# HMC5883_module.net
KiCad netlist of a schematic drawn in Altium Designer
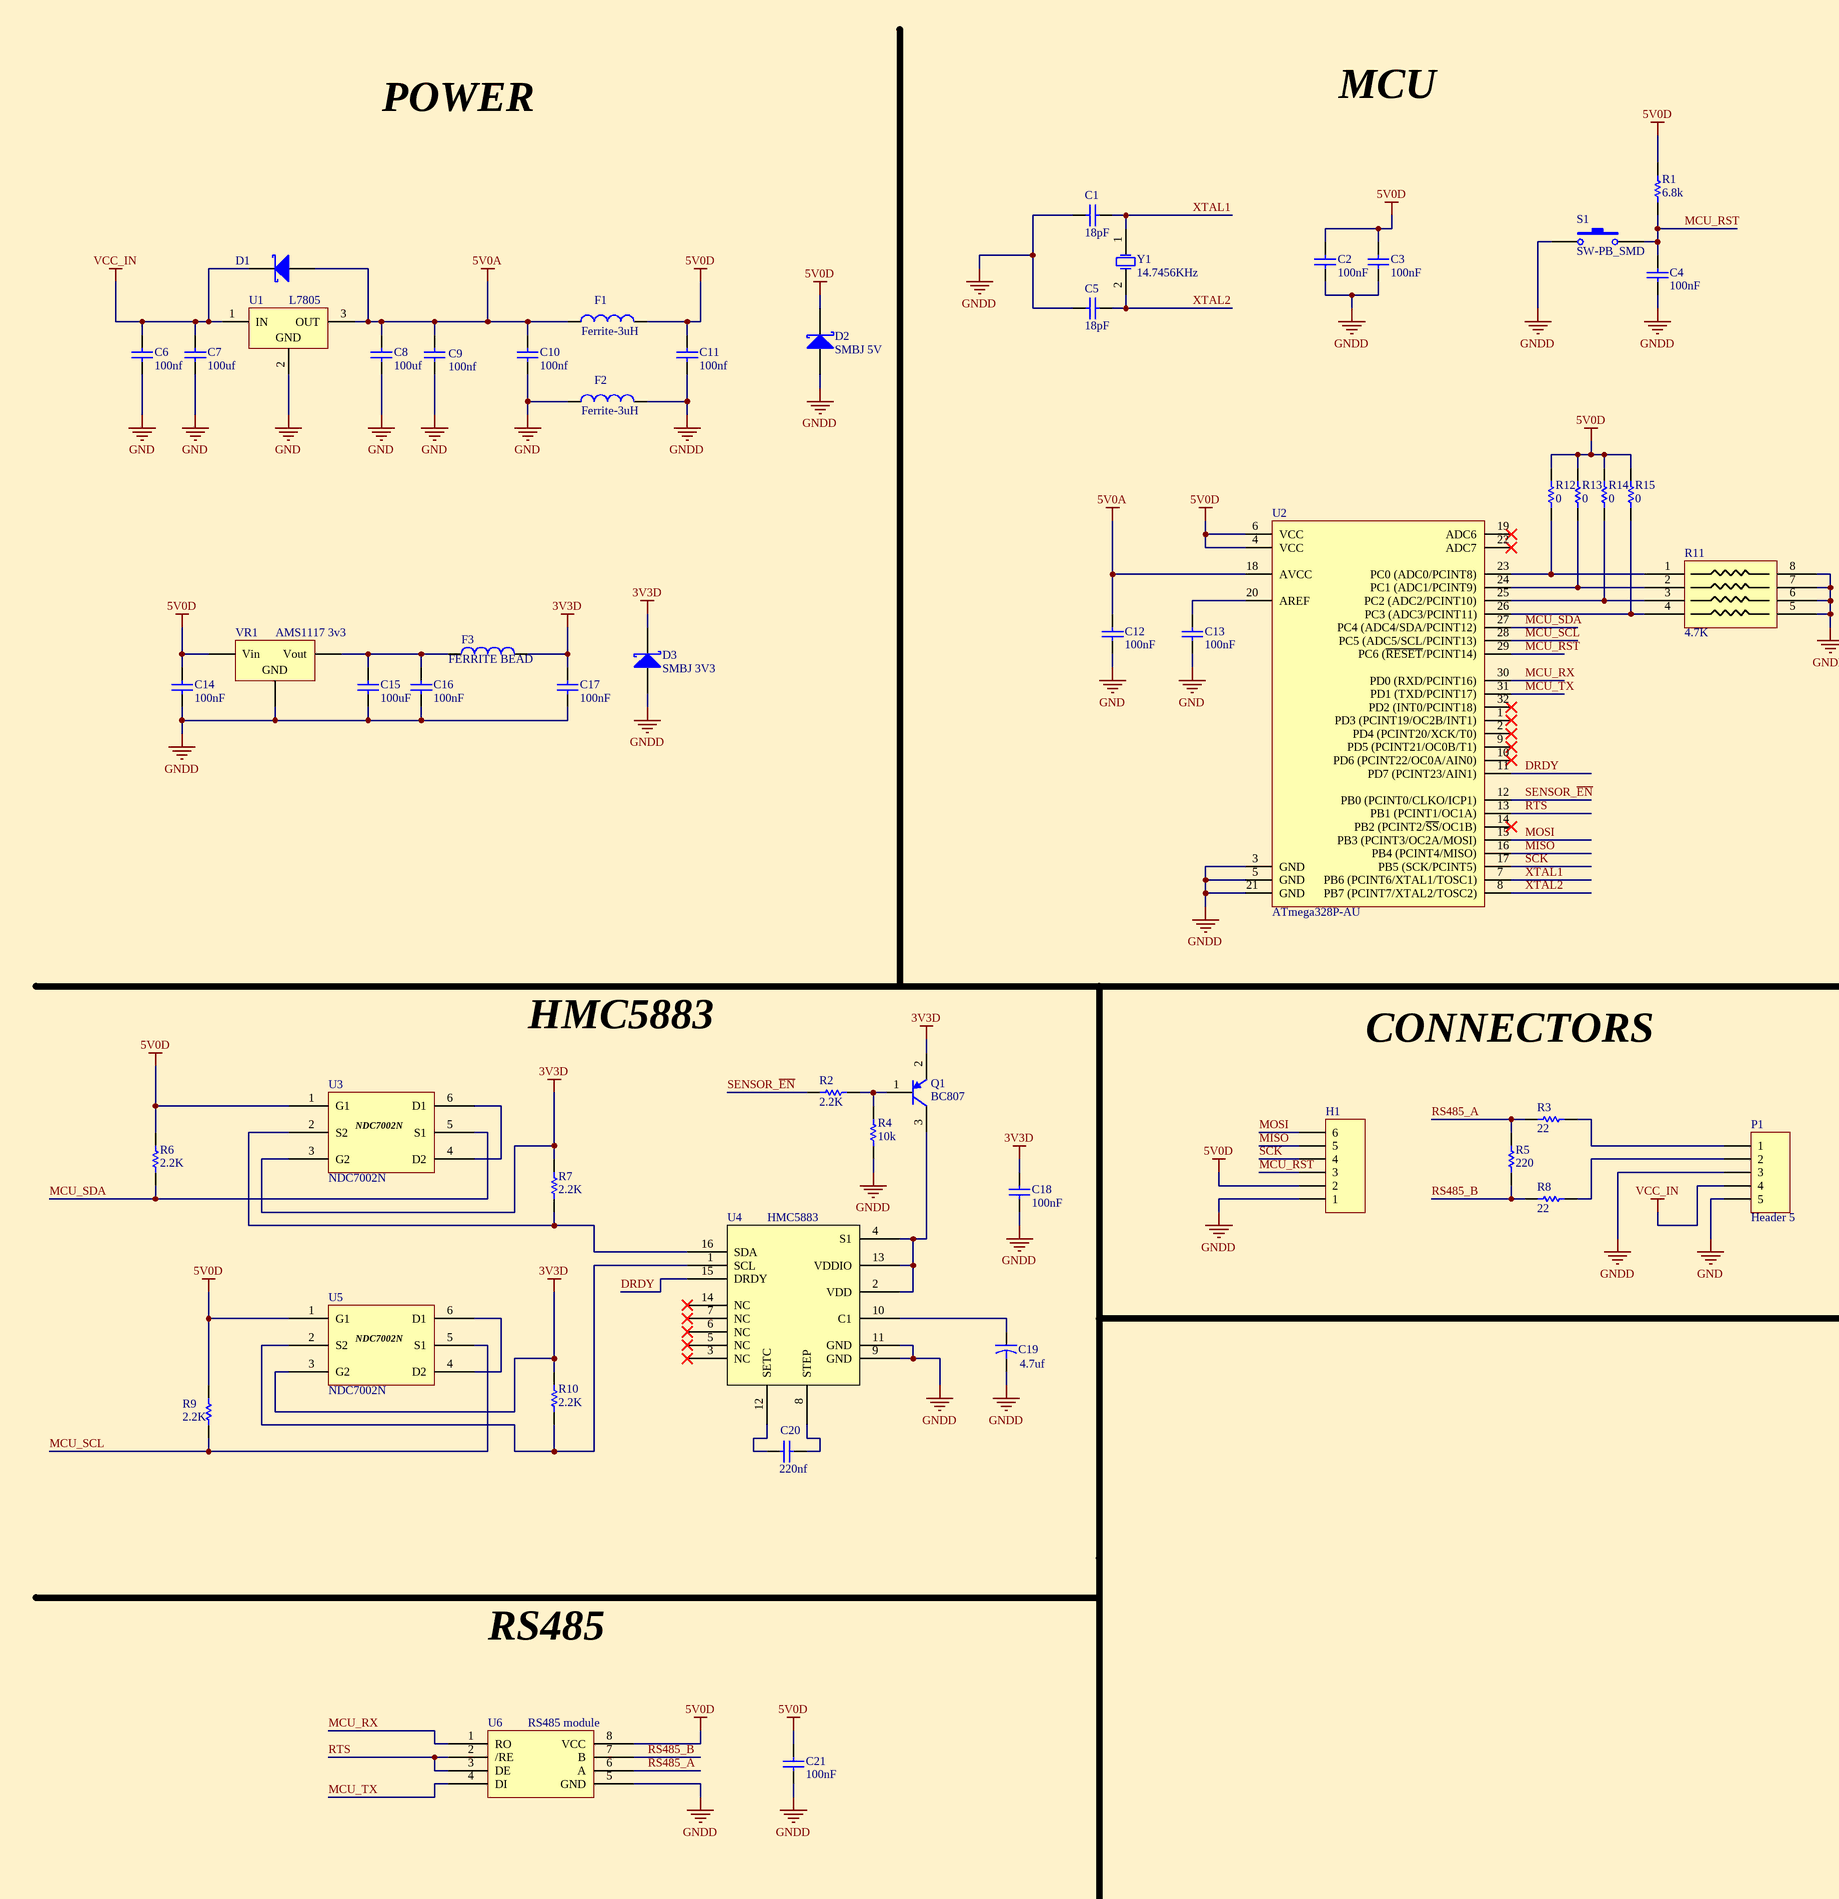
[diagram p0: HMC5883_module.SchDoc, left]
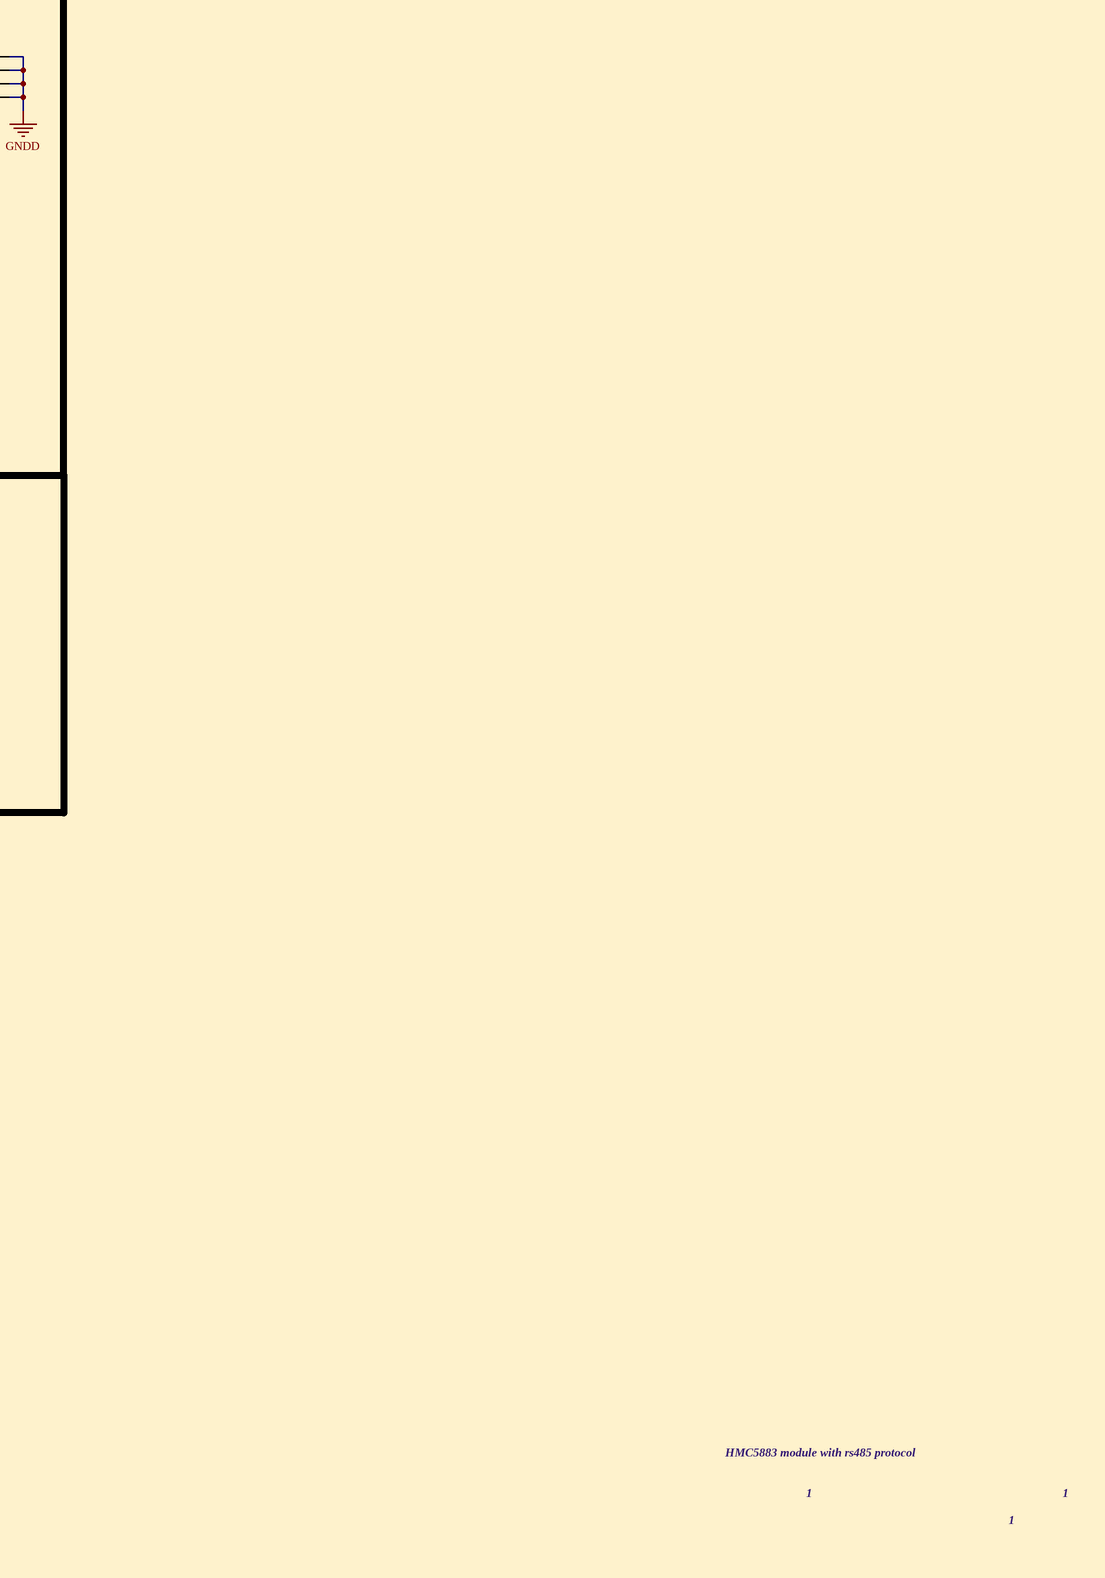
[diagram p1: HMC5883_module.SchDoc, right]

(export (version "E")
  (design (tool "Eeschema 10.0.6"))
  (components
    (comp (ref "C1")
      (value "18pF")
      (footprint "1206")
      (description "Capacitor")
      (fields (field (name "PUBLISHER") "Altium Limited"))
      (libsource (lib "Miscellaneous Devices") (part "Cap"))
    )
    (comp (ref "C2")
      (value "100nF")
      (footprint "1206")
      (description "Capacitor")
      (fields (field (name "PUBLISHER") "Altium Limited"))
      (libsource (lib "Miscellaneous Devices") (part "Cap"))
    )
    (comp (ref "C3")
      (value "100nF")
      (footprint "1206")
      (description "Capacitor")
      (fields (field (name "PUBLISHER") "Altium Limited"))
      (libsource (lib "Miscellaneous Devices") (part "Cap"))
    )
    (comp (ref "C4")
      (value "100nF")
      (footprint "1206")
      (description "Capacitor")
      (fields (field (name "PUBLISHER") "Altium Limited"))
      (libsource (lib "Miscellaneous Devices") (part "Cap"))
    )
    (comp (ref "C5")
      (value "18pF")
      (footprint "1206")
      (description "Capacitor")
      (fields (field (name "PUBLISHER") "Altium Limited"))
      (libsource (lib "Miscellaneous Devices") (part "Cap"))
    )
    (comp (ref "C6")
      (value "100nf")
      (footprint "1206")
      (description "Capacitor, 1206")
      (fields (field (name "PUBLISHER") "Altium Limited"))
      (libsource (lib "Miscellaneous Devices") (part "Cap"))
    )
    (comp (ref "C7")
      (value "100uf")
      (footprint "1206")
      (description "Capacitor, 1206")
      (fields (field (name "PUBLISHER") "Altium Limited"))
      (libsource (lib "Miscellaneous Devices") (part "Cap"))
    )
    (comp (ref "C8")
      (value "100uf")
      (footprint "1206")
      (description "Capacitor, 1206")
      (fields (field (name "PUBLISHER") "Altium Limited"))
      (libsource (lib "Miscellaneous Devices") (part "Cap"))
    )
    (comp (ref "C9")
      (value "100nf")
      (footprint "1206")
      (description "Capacitor, 1206")
      (fields (field (name "PUBLISHER") "Altium Limited"))
      (libsource (lib "Miscellaneous Devices") (part "Cap"))
    )
    (comp (ref "C10")
      (value "100nf")
      (footprint "1206")
      (description "Capacitor, 1206")
      (fields (field (name "PUBLISHER") "Altium Limited"))
      (libsource (lib "Miscellaneous Devices") (part "Cap"))
    )
    (comp (ref "C11")
      (value "100nf")
      (footprint "1206")
      (description "Capacitor, 1206")
      (fields (field (name "PUBLISHER") "Altium Limited"))
      (libsource (lib "Miscellaneous Devices") (part "Cap"))
    )
    (comp (ref "C12")
      (value "100nF")
      (footprint "1206")
      (description "Capacitor")
      (fields (field (name "PUBLISHER") "Altium Limited"))
      (libsource (lib "Miscellaneous Devices") (part "Cap"))
    )
    (comp (ref "C13")
      (value "100nF")
      (footprint "1206")
      (description "Capacitor")
      (fields (field (name "PUBLISHER") "Altium Limited"))
      (libsource (lib "Miscellaneous Devices") (part "Cap"))
    )
    (comp (ref "C14")
      (value "100nF")
      (footprint "1206")
      (description "Capacitor")
      (fields (field (name "Comment") "Cap") (field (name "PUBLISHER") "Altium Limited"))
      (libsource (lib "Miscellaneous Devices") (part "Cap"))
    )
    (comp (ref "C15")
      (value "100uF")
      (footprint "1206")
      (description "Capacitor")
      (fields (field (name "Comment") "Cap") (field (name "PUBLISHER") "Altium Limited"))
      (libsource (lib "Miscellaneous Devices") (part "Cap"))
    )
    (comp (ref "C16")
      (value "100nF")
      (footprint "1206")
      (description "Capacitor")
      (fields (field (name "Comment") "Cap") (field (name "PUBLISHER") "Altium Limited"))
      (libsource (lib "Miscellaneous Devices") (part "Cap"))
    )
    (comp (ref "C17")
      (value "100nF")
      (footprint "1206")
      (description "Capacitor")
      (fields (field (name "Comment") "Cap") (field (name "PUBLISHER") "Altium Limited"))
      (libsource (lib "Miscellaneous Devices") (part "Cap"))
    )
    (comp (ref "C18")
      (value "100nF")
      (footprint "1206")
      (description "Capacitor")
      (fields (field (name "Comment") "Cap") (field (name "PUBLISHER") "Altium Limited"))
      (libsource (lib "Miscellaneous Devices") (part "Cap"))
    )
    (comp (ref "C19")
      (value "4.7uf")
      (footprint "CAP_SMD_A")
      (description "TAN")
      (fields (field (name "Comment") "Cap2") (field (name "PUBLISHER") "Altium Limited"))
      (libsource (lib "Miscellaneous Devices") (part "Cap2"))
    )
    (comp (ref "C20")
      (value "220nf")
      (footprint "1206")
      (description "Capacitor")
      (fields (field (name "Comment") "Cap") (field (name "PUBLISHER") "Altium Limited"))
      (libsource (lib "Miscellaneous Devices") (part "Cap"))
    )
    (comp (ref "C21")
      (value "100nF")
      (footprint "1206")
      (description "Capacitor")
      (fields (field (name "Comment") "Cap") (field (name "PUBLISHER") "Altium Limited"))
      (libsource (lib "Miscellaneous Devices") (part "Cap"))
    )
    (comp (ref "D1")
      (value "D Schottky")
      (footprint "ZINER")
      (description "Schottky Diode, 1N4148")
      (fields (field (name "PUBLISHER") "Altium Limited"))
      (libsource (lib "Miscellaneous Devices") (part "D Schottky"))
    )
    (comp (ref "D2")
      (value "SMBJ 5V")
      (footprint "TVS")
      (description "Schottky Rectifier")
      (fields (field (name "PUBLISHER") "Altium Limited"))
      (libsource (lib "Miscellaneous Devices") (part "Diode 18TQ045"))
    )
    (comp (ref "D3")
      (value "SMBJ 3V3")
      (footprint "TVS")
      (description "TVS")
      (fields (field (name "PUBLISHER") "Altium Limited"))
      (libsource (lib "Miscellaneous Devices") (part "Diode 18TQ045"))
    )
    (comp (ref "F1")
      (value "Ferrite-3uH")
      (footprint "1206")
      (description "Inductor")
      (fields (field (name "PUBLISHER") "Altium Limited"))
      (libsource (lib "Miscellaneous Devices") (part "Inductor"))
    )
    (comp (ref "F2")
      (value "Ferrite-3uH")
      (footprint "1206")
      (description "Inductor")
      (fields (field (name "PUBLISHER") "Altium Limited"))
      (libsource (lib "Miscellaneous Devices") (part "Inductor"))
    )
    (comp (ref "F3")
      (value "FERRITE BEAD")
      (footprint "1206")
      (fields (field (name "PUBLISHER") "Altium Limited"))
      (libsource (lib "Miscellaneous Devices") (part "Inductor"))
    )
    (comp (ref "H1")
      (value "White SMD Connector 6pin")
      (footprint "White SMD Connector 6pin B")
      (fields (field (name "PUBLISHER") "Altium Limited"))
      (libsource (lib "Miscellaneous Connectors") (part "Header 6"))
    )
    (comp (ref "P1")
      (value "Header 5")
      (footprint "HDR1X5")
      (description "Header, 5-Pin")
      (fields (field (name "PUBLISHER") "Altium Limited"))
      (libsource (lib "Miscellaneous Connectors") (part "Header 5"))
    )
    (comp (ref "Q1")
      (value "BC807")
      (footprint "SOT-23")
      (description "PNP General Purpose Amplifier")
      (fields (field (name "PUBLISHER") "Altium Limited"))
      (libsource (lib "Miscellaneous Devices") (part "2N3906"))
    )
    (comp (ref "R1")
      (value "6.8k")
      (footprint "1206")
      (description "Resistor, 6.8k")
      (fields (field (name "PUBLISHER") "Altium Limited"))
      (libsource (lib "Miscellaneous Devices") (part "Res1"))
    )
    (comp (ref "R2")
      (value "2.2K")
      (footprint "1206")
      (description "Resistor")
      (fields (field (name "PUBLISHER") "Altium Limited"))
      (libsource (lib "Miscellaneous Devices") (part "Res1"))
    )
    (comp (ref "R3")
      (value "22")
      (footprint "1206")
      (description "Resistor")
      (fields (field (name "PUBLISHER") "Altium Limited"))
      (libsource (lib "Miscellaneous Devices") (part "Res1"))
    )
    (comp (ref "R4")
      (value "10k")
      (footprint "1206")
      (description "Resistor")
      (fields (field (name "PUBLISHER") "Altium Limited"))
      (libsource (lib "Miscellaneous Devices") (part "Res1"))
    )
    (comp (ref "R5")
      (value "220")
      (footprint "1206")
      (description "Resistor")
      (fields (field (name "PUBLISHER") "Altium Limited"))
      (libsource (lib "Miscellaneous Devices") (part "Res1"))
    )
    (comp (ref "R6")
      (value "2.2K")
      (footprint "1206")
      (description "Resistor")
      (fields (field (name "PUBLISHER") "Altium Limited"))
      (libsource (lib "Miscellaneous Devices") (part "Res1"))
    )
    (comp (ref "R7")
      (value "2.2K")
      (footprint "1206")
      (description "Resistor")
      (fields (field (name "PUBLISHER") "Altium Limited"))
      (libsource (lib "Miscellaneous Devices") (part "Res1"))
    )
    (comp (ref "R8")
      (value "22")
      (footprint "1206")
      (description "Resistor")
      (fields (field (name "PUBLISHER") "Altium Limited"))
      (libsource (lib "Miscellaneous Devices") (part "Res1"))
    )
    (comp (ref "R9")
      (value "2.2K")
      (footprint "1206")
      (description "Resistor")
      (fields (field (name "PUBLISHER") "Altium Limited"))
      (libsource (lib "Miscellaneous Devices") (part "Res1"))
    )
    (comp (ref "R10")
      (value "2.2K")
      (footprint "1206")
      (description "Resistor")
      (fields (field (name "PUBLISHER") "Altium Limited"))
      (libsource (lib "Miscellaneous Devices") (part "Res1"))
    )
    (comp (ref "R11")
      (value "4.7K")
      (footprint "RP0603X4")
      (libsource (lib "RES_ARRAY_4") (part "RES_ARRAY_4"))
    )
    (comp (ref "R12")
      (value "0")
      (footprint "0603")
      (description "Resistor, 6.8k")
      (fields (field (name "PUBLISHER") "Altium Limited"))
      (libsource (lib "Miscellaneous Devices") (part "Res1"))
    )
    (comp (ref "R13")
      (value "0")
      (footprint "0603")
      (description "Resistor, 6.8k")
      (fields (field (name "PUBLISHER") "Altium Limited"))
      (libsource (lib "Miscellaneous Devices") (part "Res1"))
    )
    (comp (ref "R14")
      (value "0")
      (footprint "0603")
      (description "Resistor, 6.8k")
      (fields (field (name "PUBLISHER") "Altium Limited"))
      (libsource (lib "Miscellaneous Devices") (part "Res1"))
    )
    (comp (ref "R15")
      (value "0")
      (footprint "0603")
      (description "Resistor, 6.8k")
      (fields (field (name "PUBLISHER") "Altium Limited"))
      (libsource (lib "Miscellaneous Devices") (part "Res1"))
    )
    (comp (ref "S1")
      (value "SW-PB_SMD")
      (footprint "PB4x3.2")
      (description "Switch")
      (fields (field (name "PUBLISHER") "Altium Limited"))
      (libsource (lib "Miscellaneous Devices") (part "SW-PB"))
    )
    (comp (ref "U1")
      (value "L7805")
      (footprint "DPAK")
      (description "Positive Voltage Regulator")
      (fields (field (name "PUBLISHER") "Altium Limited"))
      (libsource (lib "ST Power Mgt Voltage Regulator") (part "L7805CD2T"))
    )
    (comp (ref "U2")
      (value "ATmega328P-AU")
      (footprint "32A_L")
      (fields (field (name "PUBLISHER") "Altium Limited"))
      (libsource (lib "Library") (part "ATmega328P-AU"))
    )
    (comp (ref "U3") (value "NDC7002N") (footprint "SOP6") (libsource (lib "NDC7002N") (part "NDC7002N")))
    (comp (ref "U4") (value "HMC5883") (footprint "LCC16") (libsource (lib "Library") (part "HMC5883")))
    (comp (ref "U5") (value "NDC7002N") (footprint "SOP6") (libsource (lib "NDC7002N") (part "NDC7002N")))
    (comp (ref "U6")
      (value "RS485 module")
      (footprint "SOP8")
      (libsource (lib "Schlib_RS485") (part "rs485"))
    )
    (comp (ref "VR1")
      (value "AMS1117 3v3")
      (footprint "LD1117")
      (description "Voltage Regulator")
      (fields (field (name "PUBLISHER") "Altium Limited"))
      (libsource (lib "Miscellaneous Devices") (part "Volt Reg"))
    )
    (comp (ref "Y1")
      (value "14.7456KHz")
      (footprint "XTAL_SMD")
      (description "Crystal Oscillator, 14.7456KHz")
      (fields (field (name "PUBLISHER") "Altium Limited"))
      (libsource (lib "Miscellaneous Devices") (part "XTAL"))
    )
  )
  (nets
    (net (code "1") (name "/DRDY") (class "Default")
      (node (ref "U2") (pin "11") (pinfunction "PD7_(PCINT23/AIN1)_11") (pintype "passive"))
      (node (ref "U4") (pin "15") (pinfunction "DRDY_15") (pintype "passive"))
    )
    (net (code "2") (name "/MCU_RST") (class "Default")
      (node (ref "C4") (pin "2") (pinfunction "2_2") (pintype "passive"))
      (node (ref "H1") (pin "3") (pinfunction "3_3") (pintype "passive"))
      (node (ref "R1") (pin "2") (pinfunction "2_2") (pintype "passive"))
      (node (ref "S1") (pin "2") (pinfunction "2_2") (pintype "passive"))
      (node (ref "U2") (pin "29") (pinfunction "PC6_(~{RESET}/PCINT14)_29") (pintype "passive"))
    )
    (net (code "3") (name "/MCU_RX") (class "Default")
      (node (ref "U2") (pin "30") (pinfunction "PD0_(RXD/PCINT16)_30") (pintype "passive"))
      (node (ref "U6") (pin "1") (pinfunction "RO_1") (pintype "passive"))
    )
    (net (code "4") (name "/MCU_SCL") (class "Default")
      (node (ref "R9") (pin "1") (pinfunction "1_1") (pintype "passive"))
      (node (ref "U2") (pin "28") (pinfunction "PC5_(ADC5/SCL/PCINT13)_28") (pintype "passive"))
      (node (ref "U5") (pin "5") (pinfunction "S1_5") (pintype "passive"))
    )
    (net (code "5") (name "/MCU_SDA") (class "Default")
      (node (ref "R6") (pin "1") (pinfunction "1_1") (pintype "passive"))
      (node (ref "U2") (pin "27") (pinfunction "PC4_(ADC4/SDA/PCINT12)_27") (pintype "passive"))
      (node (ref "U3") (pin "5") (pinfunction "S1_5") (pintype "passive"))
    )
    (net (code "6") (name "/MCU_TX") (class "Default")
      (node (ref "U2") (pin "31") (pinfunction "PD1_(TXD/PCINT17)_31") (pintype "passive"))
      (node (ref "U6") (pin "4") (pinfunction "DI_4") (pintype "passive"))
    )
    (net (code "7") (name "/MISO") (class "Default")
      (node (ref "H1") (pin "5") (pinfunction "5_5") (pintype "passive"))
      (node (ref "U2") (pin "16") (pinfunction "PB4_(PCINT4/MISO)_16") (pintype "passive"))
    )
    (net (code "8") (name "/MOSI") (class "Default")
      (node (ref "H1") (pin "6") (pinfunction "6_6") (pintype "passive"))
      (node (ref "U2") (pin "15") (pinfunction "PB3_(PCINT3/OC2A/MOSI)_15") (pintype "passive"))
    )
    (net (code "9") (name "/RS485_A") (class "Default")
      (node (ref "R3") (pin "1") (pinfunction "1_1") (pintype "passive"))
      (node (ref "R5") (pin "1") (pinfunction "1_1") (pintype "passive"))
      (node (ref "U6") (pin "6") (pinfunction "A_6") (pintype "passive"))
    )
    (net (code "10") (name "/RS485_B") (class "Default")
      (node (ref "R5") (pin "2") (pinfunction "2_2") (pintype "passive"))
      (node (ref "R8") (pin "1") (pinfunction "1_1") (pintype "passive"))
      (node (ref "U6") (pin "7") (pinfunction "B_7") (pintype "passive"))
    )
    (net (code "11") (name "/RTS") (class "Default")
      (node (ref "U2") (pin "13") (pinfunction "PB1_(PCINT1/OC1A)_13") (pintype "passive"))
      (node (ref "U6") (pin "2") (pinfunction "/RE_2") (pintype "passive"))
      (node (ref "U6") (pin "3") (pinfunction "DE_3") (pintype "passive"))
    )
    (net (code "12") (name "/SCK") (class "Default")
      (node (ref "H1") (pin "4") (pinfunction "4_4") (pintype "passive"))
      (node (ref "U2") (pin "17") (pinfunction "PB5_(SCK/PCINT5)_17") (pintype "passive"))
    )
    (net (code "13") (name "/SENSOR_~{EN}") (class "Default")
      (node (ref "R2") (pin "2") (pinfunction "2_2") (pintype "passive"))
      (node (ref "U2") (pin "12") (pinfunction "PB0_(PCINT0/CLKO/ICP1)_12") (pintype "passive"))
    )
    (net (code "14") (name "/XTAL1") (class "Default")
      (node (ref "C1") (pin "2") (pinfunction "2_2") (pintype "passive"))
      (node (ref "U2") (pin "7") (pinfunction "PB6_(PCINT6/XTAL1/TOSC1)_7") (pintype "passive"))
      (node (ref "Y1") (pin "1") (pinfunction "OSC1_1") (pintype "passive"))
    )
    (net (code "15") (name "/XTAL2") (class "Default")
      (node (ref "C5") (pin "2") (pinfunction "2_2") (pintype "passive"))
      (node (ref "U2") (pin "8") (pinfunction "PB7_(PCINT7/XTAL2/TOSC2)_8") (pintype "passive"))
      (node (ref "Y1") (pin "2") (pinfunction "OSC2_2") (pintype "passive"))
    )
    (net (code "16") (name "3V3D") (class "Default")
      (node (ref "C17") (pin "2") (pinfunction "2_2") (pintype "passive"))
      (node (ref "C18") (pin "2") (pinfunction "2_2") (pintype "passive"))
      (node (ref "D3") (pin "1") (pinfunction "K_1") (pintype "passive"))
      (node (ref "F3") (pin "2") (pinfunction "2_2") (pintype "passive"))
      (node (ref "Q1") (pin "2") (pinfunction "E_2") (pintype "passive"))
      (node (ref "R10") (pin "2") (pinfunction "2_2") (pintype "passive"))
      (node (ref "R7") (pin "2") (pinfunction "2_2") (pintype "passive"))
      (node (ref "U3") (pin "3") (pinfunction "G2_3") (pintype "passive"))
      (node (ref "U5") (pin "3") (pinfunction "G2_3") (pintype "passive"))
    )
    (net (code "17") (name "5V0A") (class "Default")
      (node (ref "C10") (pin "2") (pinfunction "2_2") (pintype "passive"))
      (node (ref "C12") (pin "2") (pinfunction "2_2") (pintype "passive"))
      (node (ref "C8") (pin "2") (pinfunction "2_2") (pintype "passive"))
      (node (ref "C9") (pin "2") (pinfunction "2_2") (pintype "passive"))
      (node (ref "D1") (pin "1") (pinfunction "A_1") (pintype "passive"))
      (node (ref "F1") (pin "1") (pinfunction "1_1") (pintype "passive"))
      (node (ref "U1") (pin "3") (pinfunction "OUT_3") (pintype "power_in"))
      (node (ref "U2") (pin "18") (pinfunction "AVCC_18") (pintype "passive"))
    )
    (net (code "18") (name "5V0D") (class "Default")
      (node (ref "C11") (pin "2") (pinfunction "2_2") (pintype "passive"))
      (node (ref "C14") (pin "2") (pinfunction "2_2") (pintype "passive"))
      (node (ref "C2") (pin "2") (pinfunction "2_2") (pintype "passive"))
      (node (ref "C21") (pin "2") (pinfunction "2_2") (pintype "passive"))
      (node (ref "C3") (pin "2") (pinfunction "2_2") (pintype "passive"))
      (node (ref "D2") (pin "1") (pinfunction "K_1") (pintype "passive"))
      (node (ref "F1") (pin "2") (pinfunction "2_2") (pintype "passive"))
      (node (ref "H1") (pin "2") (pinfunction "2_2") (pintype "passive"))
      (node (ref "R1") (pin "1") (pinfunction "1_1") (pintype "passive"))
      (node (ref "R12") (pin "1") (pinfunction "1_1") (pintype "passive"))
      (node (ref "R13") (pin "1") (pinfunction "1_1") (pintype "passive"))
      (node (ref "R14") (pin "1") (pinfunction "1_1") (pintype "passive"))
      (node (ref "R15") (pin "1") (pinfunction "1_1") (pintype "passive"))
      (node (ref "R6") (pin "2") (pinfunction "2_2") (pintype "passive"))
      (node (ref "R9") (pin "2") (pinfunction "2_2") (pintype "passive"))
      (node (ref "U2") (pin "4") (pinfunction "VCC_4") (pintype "passive"))
      (node (ref "U2") (pin "6") (pinfunction "VCC_6") (pintype "passive"))
      (node (ref "U3") (pin "1") (pinfunction "G1_1") (pintype "passive"))
      (node (ref "U5") (pin "1") (pinfunction "G1_1") (pintype "passive"))
      (node (ref "U6") (pin "8") (pinfunction "VCC_8") (pintype "passive"))
      (node (ref "VR1") (pin "3") (pinfunction "Vin_3") (pintype "passive"))
    )
    (net (code "19") (name "GND") (class "Default")
      (node (ref "C10") (pin "1") (pinfunction "1_1") (pintype "passive"))
      (node (ref "C12") (pin "1") (pinfunction "1_1") (pintype "passive"))
      (node (ref "C13") (pin "1") (pinfunction "1_1") (pintype "passive"))
      (node (ref "C6") (pin "1") (pinfunction "1_1") (pintype "passive"))
      (node (ref "C7") (pin "1") (pinfunction "1_1") (pintype "passive"))
      (node (ref "C8") (pin "1") (pinfunction "1_1") (pintype "passive"))
      (node (ref "C9") (pin "1") (pinfunction "1_1") (pintype "passive"))
      (node (ref "F2") (pin "1") (pinfunction "1_1") (pintype "passive"))
      (node (ref "P1") (pin "5") (pinfunction "5_5") (pintype "passive"))
      (node (ref "U1") (pin "2") (pinfunction "GND_2") (pintype "power_in"))
    )
    (net (code "20") (name "GNDD") (class "Default")
      (node (ref "C1") (pin "1") (pinfunction "1_1") (pintype "passive"))
      (node (ref "C11") (pin "1") (pinfunction "1_1") (pintype "passive"))
      (node (ref "C14") (pin "1") (pinfunction "1_1") (pintype "passive"))
      (node (ref "C15") (pin "1") (pinfunction "1_1") (pintype "passive"))
      (node (ref "C16") (pin "1") (pinfunction "1_1") (pintype "passive"))
      (node (ref "C17") (pin "1") (pinfunction "1_1") (pintype "passive"))
      (node (ref "C18") (pin "1") (pinfunction "1_1") (pintype "passive"))
      (node (ref "C19") (pin "2") (pinfunction "2_2") (pintype "passive"))
      (node (ref "C2") (pin "1") (pinfunction "1_1") (pintype "passive"))
      (node (ref "C21") (pin "1") (pinfunction "1_1") (pintype "passive"))
      (node (ref "C3") (pin "1") (pinfunction "1_1") (pintype "passive"))
      (node (ref "C4") (pin "1") (pinfunction "1_1") (pintype "passive"))
      (node (ref "C5") (pin "1") (pinfunction "1_1") (pintype "passive"))
      (node (ref "D2") (pin "2") (pinfunction "A_2") (pintype "passive"))
      (node (ref "D3") (pin "2") (pinfunction "A_2") (pintype "passive"))
      (node (ref "F2") (pin "2") (pinfunction "2_2") (pintype "passive"))
      (node (ref "H1") (pin "1") (pinfunction "1_1") (pintype "passive"))
      (node (ref "P1") (pin "3") (pinfunction "3_3") (pintype "passive"))
      (node (ref "R11") (pin "5") (pinfunction "5_5") (pintype "passive"))
      (node (ref "R11") (pin "6") (pinfunction "6_6") (pintype "passive"))
      (node (ref "R11") (pin "7") (pinfunction "7_7") (pintype "passive"))
      (node (ref "R11") (pin "8") (pinfunction "8_8") (pintype "passive"))
      (node (ref "R4") (pin "2") (pinfunction "2_2") (pintype "passive"))
      (node (ref "S1") (pin "1") (pinfunction "1_1") (pintype "passive"))
      (node (ref "U2") (pin "21") (pinfunction "GND_21") (pintype "passive"))
      (node (ref "U2") (pin "3") (pinfunction "GND_3") (pintype "passive"))
      (node (ref "U2") (pin "5") (pinfunction "GND_5") (pintype "passive"))
      (node (ref "U4") (pin "11") (pinfunction "GND_11") (pintype "passive"))
      (node (ref "U4") (pin "9") (pinfunction "GND_9") (pintype "passive"))
      (node (ref "U6") (pin "5") (pinfunction "GND_5") (pintype "passive"))
      (node (ref "VR1") (pin "1") (pinfunction "GND_1") (pintype "passive"))
    )
    (net (code "21") (name "Net-(P1-Pad1)") (class "Default")
      (node (ref "P1") (pin "1") (pinfunction "1_1") (pintype "passive"))
      (node (ref "R3") (pin "2") (pinfunction "2_2") (pintype "passive"))
    )
    (net (code "22") (name "Net-(P1-Pad2)") (class "Default")
      (node (ref "P1") (pin "2") (pinfunction "2_2") (pintype "passive"))
      (node (ref "R8") (pin "2") (pinfunction "2_2") (pintype "passive"))
    )
    (net (code "23") (name "Net-(Q1-B)") (class "Default")
      (node (ref "Q1") (pin "1") (pinfunction "B_1") (pintype "passive"))
      (node (ref "R2") (pin "1") (pinfunction "1_1") (pintype "passive"))
      (node (ref "R4") (pin "1") (pinfunction "1_1") (pintype "passive"))
    )
    (net (code "24") (name "Net-(Q1-C)") (class "Default")
      (node (ref "Q1") (pin "3") (pinfunction "C_3") (pintype "passive"))
      (node (ref "U4") (pin "13") (pinfunction "VDDIO_13") (pintype "passive"))
      (node (ref "U4") (pin "2") (pinfunction "VDD_2") (pintype "passive"))
      (node (ref "U4") (pin "4") (pinfunction "S1_4") (pintype "passive"))
    )
    (net (code "25") (name "Net-(U2-AREF)") (class "Default")
      (node (ref "C13") (pin "2") (pinfunction "2_2") (pintype "passive"))
      (node (ref "U2") (pin "20") (pinfunction "AREF_20") (pintype "passive"))
    )
    (net (code "26") (name "Net-(U2-PC0_(ADC0{slash}PCINT8))") (class "Default")
      (node (ref "R11") (pin "1") (pinfunction "1_1") (pintype "passive"))
      (node (ref "R12") (pin "2") (pinfunction "2_2") (pintype "passive"))
      (node (ref "U2") (pin "23") (pinfunction "PC0_(ADC0/PCINT8)_23") (pintype "passive"))
    )
    (net (code "27") (name "Net-(U2-PC1_(ADC1{slash}PCINT9))") (class "Default")
      (node (ref "R11") (pin "2") (pinfunction "2_2") (pintype "passive"))
      (node (ref "R13") (pin "2") (pinfunction "2_2") (pintype "passive"))
      (node (ref "U2") (pin "24") (pinfunction "PC1_(ADC1/PCINT9)_24") (pintype "passive"))
    )
    (net (code "28") (name "Net-(U2-PC2_(ADC2{slash}PCINT10))") (class "Default")
      (node (ref "R11") (pin "3") (pinfunction "3_3") (pintype "passive"))
      (node (ref "R14") (pin "2") (pinfunction "2_2") (pintype "passive"))
      (node (ref "U2") (pin "25") (pinfunction "PC2_(ADC2/PCINT10)_25") (pintype "passive"))
    )
    (net (code "29") (name "Net-(U2-PC3_(ADC3{slash}PCINT11))") (class "Default")
      (node (ref "R11") (pin "4") (pinfunction "4_4") (pintype "passive"))
      (node (ref "R15") (pin "2") (pinfunction "2_2") (pintype "passive"))
      (node (ref "U2") (pin "26") (pinfunction "PC3_(ADC3/PCINT11)_26") (pintype "passive"))
    )
    (net (code "30") (name "Net-(U3-D1)") (class "Default")
      (node (ref "U3") (pin "4") (pinfunction "D2_4") (pintype "passive"))
      (node (ref "U3") (pin "6") (pinfunction "D1_6") (pintype "passive"))
    )
    (net (code "31") (name "Net-(U3-S2)") (class "Default")
      (node (ref "R7") (pin "1") (pinfunction "1_1") (pintype "passive"))
      (node (ref "U3") (pin "2") (pinfunction "S2_2") (pintype "passive"))
      (node (ref "U4") (pin "16") (pinfunction "SDA_16") (pintype "passive"))
    )
    (net (code "32") (name "Net-(U4-C1)") (class "Default")
      (node (ref "C19") (pin "1") (pinfunction "1_1") (pintype "passive"))
      (node (ref "U4") (pin "10") (pinfunction "C1_10") (pintype "passive"))
    )
    (net (code "33") (name "Net-(U4-SCL)") (class "Default")
      (node (ref "R10") (pin "1") (pinfunction "1_1") (pintype "passive"))
      (node (ref "U4") (pin "1") (pinfunction "SCL_1") (pintype "passive"))
      (node (ref "U5") (pin "2") (pinfunction "S2_2") (pintype "passive"))
    )
    (net (code "34") (name "Net-(U4-SETC)") (class "Default")
      (node (ref "C20") (pin "2") (pinfunction "2_2") (pintype "passive"))
      (node (ref "U4") (pin "12") (pinfunction "SETC_12") (pintype "passive"))
    )
    (net (code "35") (name "Net-(U4-STEP)") (class "Default")
      (node (ref "C20") (pin "1") (pinfunction "1_1") (pintype "passive"))
      (node (ref "U4") (pin "8") (pinfunction "STEP_8") (pintype "passive"))
    )
    (net (code "36") (name "Net-(U5-D1)") (class "Default")
      (node (ref "U5") (pin "4") (pinfunction "D2_4") (pintype "passive"))
      (node (ref "U5") (pin "6") (pinfunction "D1_6") (pintype "passive"))
    )
    (net (code "37") (name "Net-(VR1-Vout)") (class "Default")
      (node (ref "C15") (pin "2") (pinfunction "2_2") (pintype "passive"))
      (node (ref "C16") (pin "2") (pinfunction "2_2") (pintype "passive"))
      (node (ref "F3") (pin "1") (pinfunction "1_1") (pintype "passive"))
      (node (ref "VR1") (pin "2") (pinfunction "Vout_2") (pintype "passive"))
    )
    (net (code "38") (name "VCC_IN") (class "Default")
      (node (ref "C6") (pin "2") (pinfunction "2_2") (pintype "passive"))
      (node (ref "C7") (pin "2") (pinfunction "2_2") (pintype "passive"))
      (node (ref "D1") (pin "2") (pinfunction "K_2") (pintype "passive"))
      (node (ref "P1") (pin "4") (pinfunction "4_4") (pintype "passive"))
      (node (ref "U1") (pin "1") (pinfunction "IN_1") (pintype "power_in"))
    )
    (net (code "39") (name "unconnected-(U2-ADC6-Pad19)") (class "Default")
      (node (ref "U2") (pin "19") (pinfunction "ADC6_19") (pintype "passive+no_connect"))
    )
    (net (code "40") (name "unconnected-(U2-ADC7-Pad22)") (class "Default")
      (node (ref "U2") (pin "22") (pinfunction "ADC7_22") (pintype "passive+no_connect"))
    )
    (net (code "41") (name "unconnected-(U2-PB2_(PCINT2{slash}~{SS}{slash}OC1B)-Pad14)") (class "Default")
      (node (ref "U2") (pin "14") (pinfunction "PB2_(PCINT2/~{SS}/OC1B)_14") (pintype "passive+no_connect"))
    )
    (net (code "42") (name "unconnected-(U2-PD2_(INT0{slash}PCINT18)-Pad32)") (class "Default")
      (node (ref "U2") (pin "32") (pinfunction "PD2_(INT0/PCINT18)_32") (pintype "passive+no_connect"))
    )
    (net (code "43") (name "unconnected-(U2-PD3_(PCINT19{slash}OC2B{slash}INT1)-Pad1)") (class "Default")
      (node (ref "U2") (pin "1") (pinfunction "PD3_(PCINT19/OC2B/INT1)_1") (pintype "passive+no_connect"))
    )
    (net (code "44") (name "unconnected-(U2-PD4_(PCINT20{slash}XCK{slash}T0)-Pad2)") (class "Default")
      (node (ref "U2") (pin "2") (pinfunction "PD4_(PCINT20/XCK/T0)_2") (pintype "passive+no_connect"))
    )
    (net (code "45") (name "unconnected-(U2-PD5_(PCINT21{slash}OC0B{slash}T1)-Pad9)") (class "Default")
      (node (ref "U2") (pin "9") (pinfunction "PD5_(PCINT21/OC0B/T1)_9") (pintype "passive+no_connect"))
    )
    (net (code "46") (name "unconnected-(U2-PD6_(PCINT22{slash}OC0A{slash}AIN0)-Pad10)") (class "Default")
      (node (ref "U2") (pin "10") (pinfunction "PD6_(PCINT22/OC0A/AIN0)_10") (pintype "passive+no_connect"))
    )
    (net (code "47") (name "unconnected-(U4-NC-Pad3)") (class "Default")
      (node (ref "U4") (pin "3") (pinfunction "NC_3") (pintype "passive+no_connect"))
    )
    (net (code "48") (name "unconnected-(U4-NC-Pad5)") (class "Default")
      (node (ref "U4") (pin "5") (pinfunction "NC_5") (pintype "passive+no_connect"))
    )
    (net (code "49") (name "unconnected-(U4-NC-Pad6)") (class "Default")
      (node (ref "U4") (pin "6") (pinfunction "NC_6") (pintype "passive+no_connect"))
    )
    (net (code "50") (name "unconnected-(U4-NC-Pad7)") (class "Default")
      (node (ref "U4") (pin "7") (pinfunction "NC_7") (pintype "passive+no_connect"))
    )
    (net (code "51") (name "unconnected-(U4-NC-Pad14)") (class "Default")
      (node (ref "U4") (pin "14") (pinfunction "NC_14") (pintype "passive+no_connect"))
    )
  )
)
